# MCP4725_V03_R00.net
KiCad netlist of a schematic drawn in Altium Designer
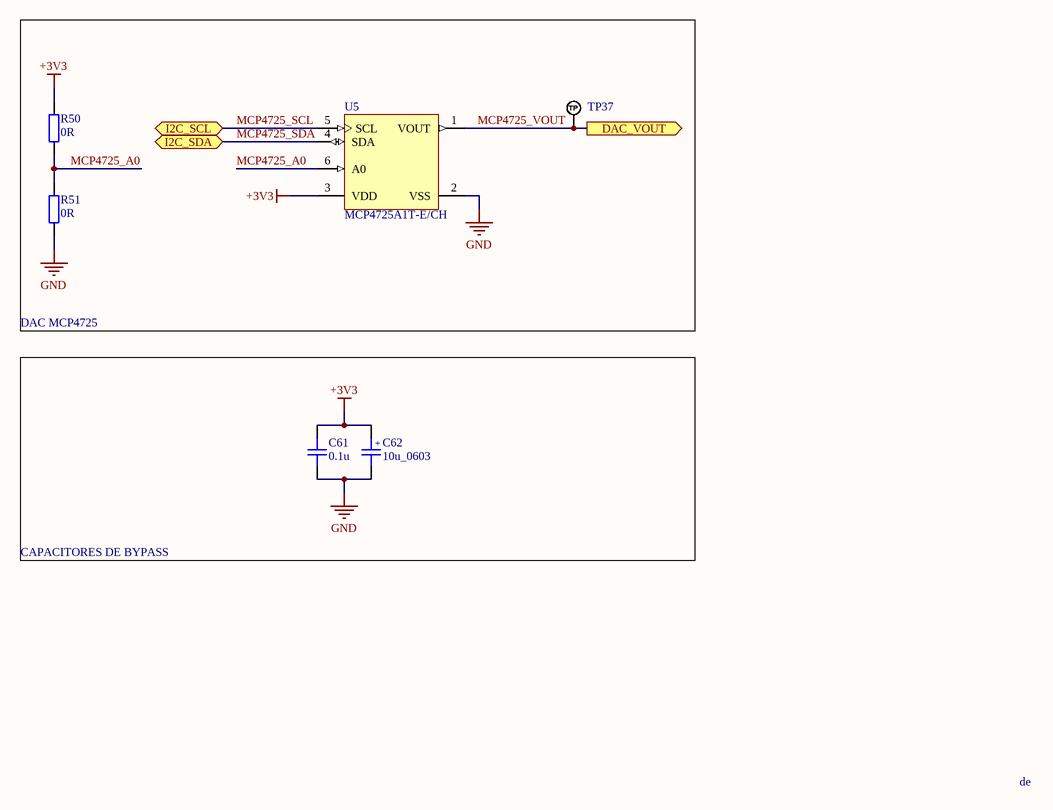
[diagram p0: MCP4725.V03.R00.SchDoc]

(export (version "E")
  (design (tool "Eeschema 10.0.6"))
  (components
    (comp (ref "C61")
      (value "0.1u")
      (footprint "CAP_0805")
      (description "Capacitor SMD 0805")
      (libsource (lib "Schematic-Lib-PhilsLab") (part "CAP_0805"))
    )
    (comp (ref "C62")
      (value "10u_0603")
      (footprint "CAP_TANT_0603")
      (description "Capacitor SMD Tantalum 0603")
      (libsource (lib "Schematic-Lib-PhilsLab") (part "CAP_TANT_0603"))
    )
    (comp (ref "R50")
      (value "0R")
      (footprint "RES_0805")
      (description "Resistor SMD 0805")
      (libsource (lib "Schematic-Lib-PhilsLab") (part "RES_0805"))
    )
    (comp (ref "R51")
      (value "0R")
      (footprint "RES_0805")
      (description "Resistor SMD 0805")
      (libsource (lib "Schematic-Lib-PhilsLab") (part "RES_0805"))
    )
    (comp (ref "TP37")
      (value "TP_NOBOM")
      (footprint "PAD_RND_1MM")
      (description "Test Point Round 1mm (NO BOM)")
      (libsource (lib "Schematic-Lib-PhilsLab") (part "TEST_POINT_RND_1MM"))
    )
    (comp (ref "U5")
      (value "MCP4725A1T-E/CH")
      (footprint "SOT-23-CH6_N")
      (libsource (lib "Altium Content Vault") (part "CON-DAC-MCP4725-6"))
    )
  )
  (nets
    (net (code "1") (name "+3V3") (class "Default")
      (node (ref "C61") (pin "1") (pinfunction "1_1") (pintype "passive"))
      (node (ref "C62") (pin "A") (pinfunction "A_A") (pintype "passive"))
      (node (ref "R50") (pin "2") (pinfunction "2_2") (pintype "passive"))
      (node (ref "U5") (pin "3") (pinfunction "VDD_3") (pintype "power_in"))
    )
    (net (code "2") (name "/MCP4725_A0") (class "Default")
      (node (ref "R50") (pin "1") (pinfunction "1_1") (pintype "passive"))
      (node (ref "R51") (pin "2") (pinfunction "2_2") (pintype "passive"))
      (node (ref "U5") (pin "6") (pinfunction "A0_6") (pintype "input"))
    )
    (net (code "3") (name "/MCP4725_SCL") (class "Default")
      (node (ref "U5") (pin "5") (pinfunction "SCL_5") (pintype "input"))
    )
    (net (code "4") (name "/MCP4725_SDA") (class "Default")
      (node (ref "U5") (pin "4") (pinfunction "SDA_4") (pintype "bidirectional"))
    )
    (net (code "5") (name "/MCP4725_VOUT") (class "Default")
      (node (ref "TP37") (pin "1") (pinfunction "TP_1") (pintype "passive"))
      (node (ref "U5") (pin "1") (pinfunction "VOUT_1") (pintype "output"))
    )
    (net (code "6") (name "GND") (class "Default")
      (node (ref "C61") (pin "2") (pinfunction "2_2") (pintype "passive"))
      (node (ref "C62") (pin "K") (pinfunction "K_K") (pintype "passive"))
      (node (ref "R51") (pin "1") (pinfunction "1_1") (pintype "passive"))
      (node (ref "U5") (pin "2") (pinfunction "VSS_2") (pintype "power_in"))
    )
  )
)
